# Wireless.net
KiCad netlist of a schematic drawn in Altium Designer
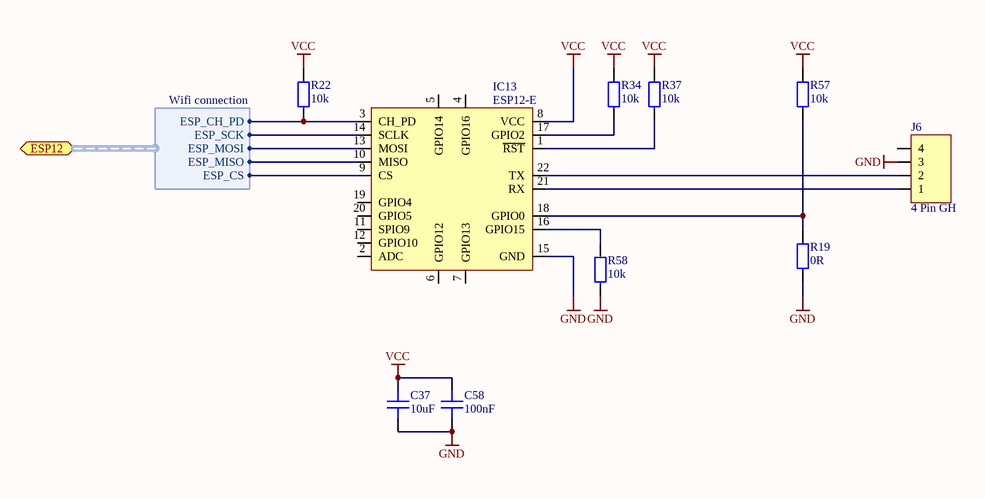
[diagram p0: Wireless.SchDoc]

(export (version "E")
  (design (tool "Eeschema 10.0.6"))
  (components
    (comp (ref "C37")
      (value "10uF")
      (footprint "CAP 0603")
      (description "SMT Capacitor")
      (libsource (lib "Passive") (part "Capacitor"))
    )
    (comp (ref "C58")
      (value "100nF")
      (footprint "CAP 0603")
      (description "SMT Capacitor")
      (libsource (lib "Passive") (part "Capacitor"))
    )
    (comp (ref "IC13")
      (value "ESP12-E")
      (footprint "ESP8266 ESP-12-E")
      (description "Wifi module, esp12-e, based on ESP8266 chip")
      (libsource (lib "uC") (part "ESP-12E"))
    )
    (comp (ref "J6")
      (value "4 Pin GH")
      (footprint "BM04B")
      (description "Złącze GH, męskie, proste, 4 piny, SMD")
      (libsource (lib "Connectors") (part "4 Pin GH"))
    )
    (comp (ref "R19")
      (value "0R")
      (footprint "RES 0603")
      (description "SMDResistor")
      (libsource (lib "Passive") (part "Resistor"))
    )
    (comp (ref "R22")
      (value "10k")
      (footprint "RES 0603")
      (description "SMDResistor")
      (libsource (lib "Passive") (part "Resistor"))
    )
    (comp (ref "R34")
      (value "10k")
      (footprint "RES 0603")
      (description "SMDResistor")
      (libsource (lib "Passive") (part "Resistor"))
    )
    (comp (ref "R37")
      (value "10k")
      (footprint "RES 0603")
      (description "SMDResistor")
      (libsource (lib "Passive") (part "Resistor"))
    )
    (comp (ref "R57")
      (value "10k")
      (footprint "RES 0603")
      (description "SMDResistor")
      (libsource (lib "Passive") (part "Resistor"))
    )
    (comp (ref "R58")
      (value "10k")
      (footprint "RES 0603")
      (description "SMDResistor")
      (libsource (lib "Passive") (part "Resistor"))
    )
  )
  (nets
    (net (code "3") (name "/ESP_CH_PD") (class "Default")
      (node (ref "IC13") (pin "3") (pinfunction "CH_PD_3") (pintype "passive"))
      (node (ref "R22") (pin "1") (pinfunction "1_1") (pintype "passive"))
    )
    (net (code "4") (name "/ESP_CS") (class "Default")
      (node (ref "IC13") (pin "9") (pinfunction "CS_9") (pintype "passive"))
    )
    (net (code "5") (name "/ESP_MISO") (class "Default")
      (node (ref "IC13") (pin "10") (pinfunction "MISO_10") (pintype "passive"))
    )
    (net (code "6") (name "/ESP_MOSI") (class "Default")
      (node (ref "IC13") (pin "13") (pinfunction "MOSI_13") (pintype "passive"))
    )
    (net (code "7") (name "/ESP_SCK") (class "Default")
      (node (ref "IC13") (pin "14") (pinfunction "SCLK_14") (pintype "passive"))
    )
    (net (code "9") (name "GND") (class "Default")
      (node (ref "C37") (pin "1") (pinfunction "1_1") (pintype "passive"))
      (node (ref "C58") (pin "1") (pinfunction "1_1") (pintype "passive"))
      (node (ref "IC13") (pin "15") (pinfunction "GND_15") (pintype "passive"))
      (node (ref "J6") (pin "3") (pinfunction "3_3") (pintype "passive"))
      (node (ref "R19") (pin "1") (pinfunction "1_1") (pintype "passive"))
      (node (ref "R58") (pin "1") (pinfunction "1_1") (pintype "passive"))
    )
    (net (code "10") (name "Net-(IC13-GPIO0)") (class "Default")
      (node (ref "IC13") (pin "18") (pinfunction "GPIO0_18") (pintype "passive"))
      (node (ref "R19") (pin "2") (pinfunction "2_2") (pintype "passive"))
      (node (ref "R57") (pin "1") (pinfunction "1_1") (pintype "passive"))
    )
    (net (code "11") (name "Net-(IC13-GPIO2)") (class "Default")
      (node (ref "IC13") (pin "17") (pinfunction "GPIO2_17") (pintype "passive"))
      (node (ref "R34") (pin "1") (pinfunction "1_1") (pintype "passive"))
    )
    (net (code "12") (name "Net-(IC13-GPIO15)") (class "Default")
      (node (ref "IC13") (pin "16") (pinfunction "GPIO15_16") (pintype "passive"))
      (node (ref "R58") (pin "2") (pinfunction "2_2") (pintype "passive"))
    )
    (net (code "13") (name "Net-(IC13-RX)") (class "Default")
      (node (ref "IC13") (pin "21") (pinfunction "RX_21") (pintype "passive"))
      (node (ref "J6") (pin "1") (pinfunction "1_1") (pintype "passive"))
    )
    (net (code "14") (name "Net-(IC13-TX)") (class "Default")
      (node (ref "IC13") (pin "22") (pinfunction "TX_22") (pintype "passive"))
      (node (ref "J6") (pin "2") (pinfunction "2_2") (pintype "passive"))
    )
    (net (code "15") (name "Net-(IC13-~{RST})") (class "Default")
      (node (ref "IC13") (pin "1") (pinfunction "~{RST}_1") (pintype "passive"))
      (node (ref "R37") (pin "1") (pinfunction "1_1") (pintype "passive"))
    )
    (net (code "16") (name "VCC") (class "Default")
      (node (ref "C37") (pin "2") (pinfunction "2_2") (pintype "passive"))
      (node (ref "C58") (pin "2") (pinfunction "2_2") (pintype "passive"))
      (node (ref "IC13") (pin "8") (pinfunction "VCC_8") (pintype "passive"))
      (node (ref "R22") (pin "2") (pinfunction "2_2") (pintype "passive"))
      (node (ref "R34") (pin "2") (pinfunction "2_2") (pintype "passive"))
      (node (ref "R37") (pin "2") (pinfunction "2_2") (pintype "passive"))
      (node (ref "R57") (pin "2") (pinfunction "2_2") (pintype "passive"))
    )
    (net (code "17") (name "unconnected-(IC13-ADC-Pad2)") (class "Default")
      (node (ref "IC13") (pin "2") (pinfunction "ADC_2") (pintype "passive"))
    )
    (net (code "18") (name "unconnected-(IC13-GPIO4-Pad19)") (class "Default")
      (node (ref "IC13") (pin "19") (pinfunction "GPIO4_19") (pintype "passive"))
    )
    (net (code "19") (name "unconnected-(IC13-GPIO5-Pad20)") (class "Default")
      (node (ref "IC13") (pin "20") (pinfunction "GPIO5_20") (pintype "passive"))
    )
    (net (code "20") (name "unconnected-(IC13-GPIO10-Pad12)") (class "Default")
      (node (ref "IC13") (pin "12") (pinfunction "GPIO10_12") (pintype "passive"))
    )
    (net (code "21") (name "unconnected-(IC13-GPIO12-Pad6)") (class "Default")
      (node (ref "IC13") (pin "6") (pinfunction "GPIO12_6") (pintype "passive"))
    )
    (net (code "22") (name "unconnected-(IC13-GPIO13-Pad7)") (class "Default")
      (node (ref "IC13") (pin "7") (pinfunction "GPIO13_7") (pintype "passive"))
    )
    (net (code "23") (name "unconnected-(IC13-GPIO14-Pad5)") (class "Default")
      (node (ref "IC13") (pin "5") (pinfunction "GPIO14_5") (pintype "passive"))
    )
    (net (code "24") (name "unconnected-(IC13-GPIO16-Pad4)") (class "Default")
      (node (ref "IC13") (pin "4") (pinfunction "GPIO16_4") (pintype "passive"))
    )
    (net (code "25") (name "unconnected-(IC13-SPIO9-Pad11)") (class "Default")
      (node (ref "IC13") (pin "11") (pinfunction "SPIO9_11") (pintype "passive"))
    )
    (net (code "26") (name "unconnected-(J6-Pad4)") (class "Default")
      (node (ref "J6") (pin "4") (pinfunction "4_4") (pintype "passive"))
    )
  )
)
